# 51control.net
KiCad netlist of a schematic drawn in Altium Designer
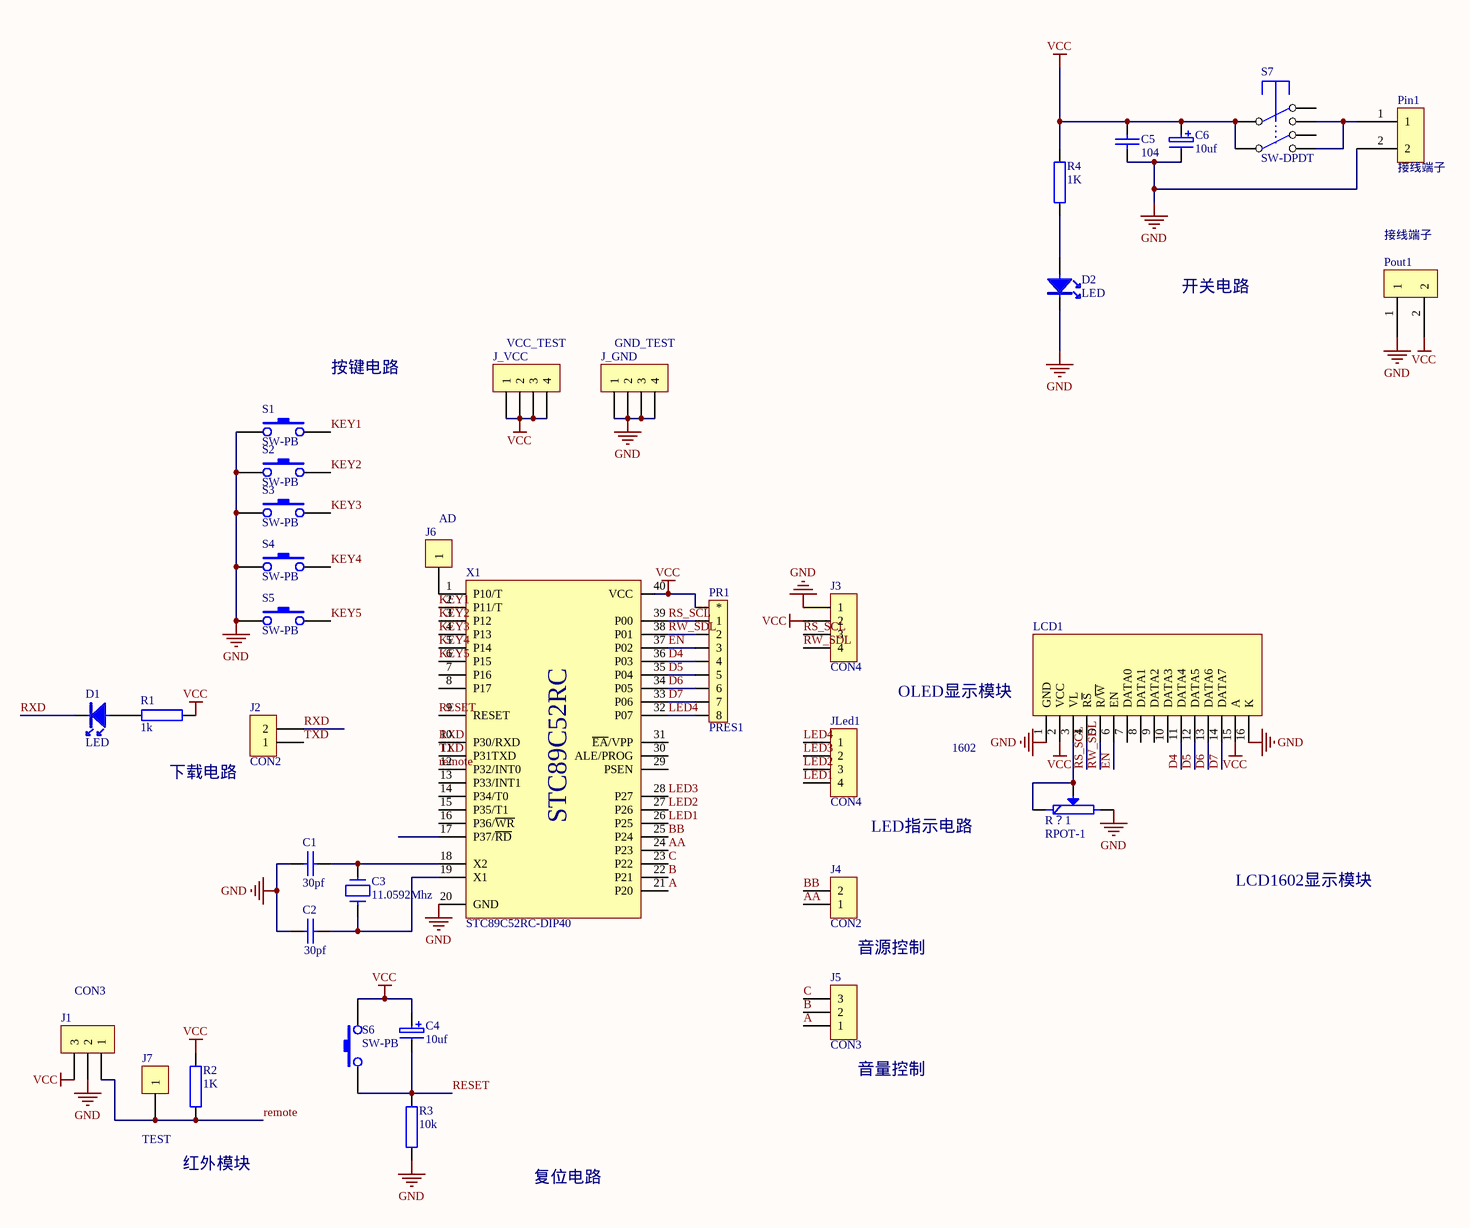
[diagram p0: 51control.SchDoc]

(export (version "E")
  (design (tool "Eeschema 10.0.6"))
  (components
    (comp (ref "C1") (value "30pf") (footprint "CAP2") (libsource (lib "电容") (part "CAP1")))
    (comp (ref "C2") (value "30pf") (footprint "CAP2") (libsource (lib "电容") (part "CAP1")))
    (comp (ref "C3") (value "11.0592Mhz") (footprint "XTAL1") (libsource (lib "晶振") (part "CPY")))
    (comp (ref "C4") (value "10uf") (footprint "CAO1") (libsource (lib "电容") (part "CAP3")))
    (comp (ref "C5") (value "104") (footprint "CAP2") (libsource (lib "电容") (part "CAP1")))
    (comp (ref "C6") (value "10uf") (footprint "CAO2") (libsource (lib "电容") (part "CAP3")))
    (comp (ref "D1") (value "LED") (footprint "LED2_B") (libsource (lib "二极管") (part "LED")))
    (comp (ref "D2") (value "LED") (footprint "LED2_B") (libsource (lib "二极管") (part "LED")))
    (comp (ref "J1")
      (value "CON3")
      (footprint "sip-3")
      (description "Connector")
      (libsource (lib "") (part "CON3_1"))
    )
    (comp (ref "J2")
      (value "CON2")
      (footprint "sip-2")
      (description "Connector")
      (libsource (lib "") (part "CON2_1"))
    )
    (comp (ref "J3")
      (value "CON4")
      (footprint "sip-4")
      (description "Connector")
      (libsource (lib "") (part "CON4_1"))
    )
    (comp (ref "J4")
      (value "CON2")
      (footprint "sip-2")
      (description "Connector")
      (libsource (lib "排针") (part "CON2"))
    )
    (comp (ref "J5")
      (value "CON3")
      (footprint "sip-3")
      (description "Connector")
      (libsource (lib "排针") (part "CON3"))
    )
    (comp (ref "J6")
      (value "AD")
      (footprint "SIP-1")
      (description "Connector")
      (libsource (lib "排针") (part "CON1"))
    )
    (comp (ref "J7")
      (value "TEST")
      (footprint "SIP-1")
      (description "Connector")
      (libsource (lib "排针") (part "CON1"))
    )
    (comp (ref "JLed1")
      (value "CON4")
      (footprint "sip-4")
      (description "Connector")
      (libsource (lib "") (part "CON4_1"))
    )
    (comp (ref "J_GND")
      (value "GND_TEST")
      (footprint "sip-4")
      (description "Connector")
      (libsource (lib "排针") (part "CON4"))
    )
    (comp (ref "J_VCC")
      (value "VCC_TEST")
      (footprint "sip-4")
      (description "Connector")
      (libsource (lib "排针") (part "CON4"))
    )
    (comp (ref "LCD1") (value "1602") (footprint "1602") (libsource (lib "液晶_数码管") (part "1602")))
    (comp (ref "Pin1") (value "接线端子") (footprint "音频功放自画库:接线端子") (libsource (lib "") (part "接线端子_1")))
    (comp (ref "Pout1") (value "接线端子") (footprint "音频功放自画库:接线端子") (libsource (lib "音频功放自画库") (part "接线端子")))
    (comp (ref "PR1") (value "PRES1") (footprint "RP1") (libsource (lib "电阻") (part "PRES1")))
    (comp (ref "R1")
      (value "1k")
      (footprint "AXIAL0.5")
      (description "电阻")
      (libsource (lib "电阻") (part "RES"))
    )
    (comp (ref "R2")
      (value "1K")
      (footprint "AXIAL0.5")
      (description "电阻")
      (libsource (lib "电阻") (part "RES"))
    )
    (comp (ref "R3")
      (value "10k")
      (footprint "AXIAL0.5")
      (description "电阻")
      (libsource (lib "电阻") (part "RES"))
    )
    (comp (ref "R4")
      (value "1K")
      (footprint "AXIAL0.5")
      (description "电阻")
      (libsource (lib "电阻") (part "RES"))
    )
    (comp (ref "R？1")
      (value "RPOT-1")
      (footprint "RVR-2")
      (description "普通电位器")
      (libsource (lib "电阻") (part "RPOT-1"))
    )
    (comp (ref "S1") (value "SW-PB") (footprint "SW6*6") (libsource (lib "开关") (part "SW-PB")))
    (comp (ref "S2") (value "SW-PB") (footprint "SW6*6") (libsource (lib "开关") (part "SW-PB")))
    (comp (ref "S3") (value "SW-PB") (footprint "SW6*6") (libsource (lib "开关") (part "SW-PB")))
    (comp (ref "S4") (value "SW-PB") (footprint "SW6*6") (libsource (lib "开关") (part "SW-PB")))
    (comp (ref "S5") (value "SW-PB") (footprint "SW6*6") (libsource (lib "开关") (part "SW-PB")))
    (comp (ref "S6") (value "SW-PB") (footprint "SW6*6") (libsource (lib "开关") (part "SW-PB")))
    (comp (ref "S7") (value "SW-DPDT") (footprint "SWH8*8") (libsource (lib "开关") (part "SW-DPDT")))
    (comp (ref "X1")
      (value "STC89C52RC-DIP40")
      (footprint "DIP-40SJ")
      (libsource (lib "单片机") (part "STC89C52RC-DIP40"))
    )
  )
  (nets
    (net (code "1") (name "/A") (class "Default")
      (node (ref "J5") (pin "1") (pinfunction "1_1") (pintype "passive"))
      (node (ref "X1") (pin "21") (pinfunction "P20_21") (pintype "passive"))
    )
    (net (code "2") (name "/AA") (class "Default")
      (node (ref "J4") (pin "1") (pinfunction "1_1") (pintype "passive"))
      (node (ref "X1") (pin "24") (pinfunction "P23_24") (pintype "passive"))
    )
    (net (code "3") (name "/B") (class "Default")
      (node (ref "J5") (pin "2") (pinfunction "2_2") (pintype "passive"))
      (node (ref "X1") (pin "22") (pinfunction "P21_22") (pintype "passive"))
    )
    (net (code "4") (name "/BB") (class "Default")
      (node (ref "J4") (pin "2") (pinfunction "2_2") (pintype "passive"))
      (node (ref "X1") (pin "25") (pinfunction "P24_25") (pintype "passive"))
    )
    (net (code "5") (name "/C") (class "Default")
      (node (ref "J5") (pin "3") (pinfunction "3_3") (pintype "passive"))
      (node (ref "X1") (pin "23") (pinfunction "P22_23") (pintype "passive"))
    )
    (net (code "6") (name "/D4") (class "Default")
      (node (ref "LCD1") (pin "11") (pinfunction "DATA4_11") (pintype "passive"))
      (node (ref "PR1") (pin "5") (pinfunction "4_5") (pintype "passive"))
      (node (ref "X1") (pin "36") (pinfunction "P03_36") (pintype "passive"))
    )
    (net (code "7") (name "/D5") (class "Default")
      (node (ref "LCD1") (pin "12") (pinfunction "DATA5_12") (pintype "passive"))
      (node (ref "PR1") (pin "6") (pinfunction "5_6") (pintype "passive"))
      (node (ref "X1") (pin "35") (pinfunction "P04_35") (pintype "passive"))
    )
    (net (code "8") (name "/D6") (class "Default")
      (node (ref "LCD1") (pin "13") (pinfunction "DATA6_13") (pintype "passive"))
      (node (ref "PR1") (pin "7") (pinfunction "6_7") (pintype "passive"))
      (node (ref "X1") (pin "34") (pinfunction "P05_34") (pintype "passive"))
    )
    (net (code "9") (name "/D7") (class "Default")
      (node (ref "LCD1") (pin "14") (pinfunction "DATA7_14") (pintype "passive"))
      (node (ref "PR1") (pin "8") (pinfunction "7_8") (pintype "passive"))
      (node (ref "X1") (pin "33") (pinfunction "P06_33") (pintype "passive"))
    )
    (net (code "10") (name "/EN") (class "Default")
      (node (ref "LCD1") (pin "6") (pinfunction "EN_6") (pintype "passive"))
      (node (ref "PR1") (pin "4") (pinfunction "3_4") (pintype "passive"))
      (node (ref "X1") (pin "37") (pinfunction "P02_37") (pintype "passive"))
    )
    (net (code "11") (name "/KEY1") (class "Default")
      (node (ref "S1") (pin "2") (pinfunction "2_2") (pintype "passive"))
      (node (ref "X1") (pin "2") (pinfunction "P11/T_2") (pintype "passive"))
    )
    (net (code "12") (name "/KEY2") (class "Default")
      (node (ref "S2") (pin "2") (pinfunction "2_2") (pintype "passive"))
      (node (ref "X1") (pin "3") (pinfunction "P12_3") (pintype "passive"))
    )
    (net (code "13") (name "/KEY3") (class "Default")
      (node (ref "S3") (pin "2") (pinfunction "2_2") (pintype "passive"))
      (node (ref "X1") (pin "4") (pinfunction "P13_4") (pintype "passive"))
    )
    (net (code "14") (name "/KEY4") (class "Default")
      (node (ref "S4") (pin "2") (pinfunction "2_2") (pintype "passive"))
      (node (ref "X1") (pin "5") (pinfunction "P14_5") (pintype "passive"))
    )
    (net (code "15") (name "/KEY5") (class "Default")
      (node (ref "S5") (pin "2") (pinfunction "2_2") (pintype "passive"))
      (node (ref "X1") (pin "6") (pinfunction "P15_6") (pintype "passive"))
    )
    (net (code "16") (name "/LED1") (class "Default")
      (node (ref "JLed1") (pin "4") (pinfunction "4_4") (pintype "passive"))
      (node (ref "X1") (pin "26") (pinfunction "P25_26") (pintype "passive"))
    )
    (net (code "17") (name "/LED2") (class "Default")
      (node (ref "JLed1") (pin "3") (pinfunction "3_3") (pintype "passive"))
      (node (ref "X1") (pin "27") (pinfunction "P26_27") (pintype "passive"))
    )
    (net (code "18") (name "/LED3") (class "Default")
      (node (ref "JLed1") (pin "2") (pinfunction "2_2") (pintype "passive"))
      (node (ref "X1") (pin "28") (pinfunction "P27_28") (pintype "passive"))
    )
    (net (code "19") (name "/LED4") (class "Default")
      (node (ref "JLed1") (pin "1") (pinfunction "1_1") (pintype "passive"))
      (node (ref "PR1") (pin "9") (pinfunction "8_9") (pintype "passive"))
      (node (ref "X1") (pin "32") (pinfunction "P07_32") (pintype "passive"))
    )
    (net (code "20") (name "/RESET") (class "Default")
      (node (ref "C4") (pin "2") (pintype "passive"))
      (node (ref "R3") (pin "2") (pinfunction "2_2") (pintype "passive"))
      (node (ref "S6") (pin "1") (pinfunction "1_1") (pintype "passive"))
      (node (ref "X1") (pin "9") (pinfunction "RESET_9") (pintype "passive"))
    )
    (net (code "21") (name "/RS_SCL") (class "Default")
      (node (ref "J3") (pin "3") (pinfunction "3_3") (pintype "passive"))
      (node (ref "LCD1") (pin "4") (pinfunction "R~{S}_4") (pintype "passive"))
      (node (ref "PR1") (pin "2") (pinfunction "1_2") (pintype "passive"))
      (node (ref "X1") (pin "39") (pinfunction "P00_39") (pintype "passive"))
    )
    (net (code "22") (name "/RW_SDL") (class "Default")
      (node (ref "J3") (pin "4") (pinfunction "4_4") (pintype "passive"))
      (node (ref "LCD1") (pin "5") (pinfunction "R/~{W}_5") (pintype "passive"))
      (node (ref "PR1") (pin "3") (pinfunction "2_3") (pintype "passive"))
      (node (ref "X1") (pin "38") (pinfunction "P01_38") (pintype "passive"))
    )
    (net (code "23") (name "/RXD") (class "Default")
      (node (ref "D1") (pin "2") (pinfunction "2_2") (pintype "passive"))
      (node (ref "J2") (pin "2") (pinfunction "2_2") (pintype "passive"))
      (node (ref "X1") (pin "10") (pinfunction "P30/RXD_10") (pintype "passive"))
    )
    (net (code "24") (name "/TXD") (class "Default")
      (node (ref "J2") (pin "1") (pinfunction "1_1") (pintype "passive"))
      (node (ref "X1") (pin "11") (pinfunction "P31TXD_11") (pintype "passive"))
    )
    (net (code "25") (name "/remote") (class "Default")
      (node (ref "J1") (pin "1") (pinfunction "1_1") (pintype "passive"))
      (node (ref "J7") (pin "1") (pinfunction "1_1") (pintype "passive"))
      (node (ref "R2") (pin "1") (pinfunction "1_1") (pintype "passive"))
      (node (ref "X1") (pin "12") (pinfunction "P32/INT0_12") (pintype "passive"))
    )
    (net (code "26") (name "GND") (class "Default")
      (node (ref "C1") (pin "2") (pinfunction "2_2") (pintype "passive"))
      (node (ref "C2") (pin "2") (pinfunction "2_2") (pintype "passive"))
      (node (ref "C5") (pin "2") (pinfunction "2_2") (pintype "passive"))
      (node (ref "C6") (pin "2") (pintype "passive"))
      (node (ref "D2") (pin "2") (pinfunction "2_2") (pintype "passive"))
      (node (ref "J1") (pin "2") (pinfunction "2_2") (pintype "passive"))
      (node (ref "J3") (pin "1") (pinfunction "1_1") (pintype "passive"))
      (node (ref "J_GND") (pin "1") (pinfunction "1_1") (pintype "passive"))
      (node (ref "J_GND") (pin "2") (pinfunction "2_2") (pintype "passive"))
      (node (ref "J_GND") (pin "3") (pinfunction "3_3") (pintype "passive"))
      (node (ref "J_GND") (pin "4") (pinfunction "4_4") (pintype "passive"))
      (node (ref "LCD1") (pin "1") (pinfunction "GND_1") (pintype "passive"))
      (node (ref "LCD1") (pin "16") (pinfunction "K_16") (pintype "passive"))
      (node (ref "Pin1") (pin "2") (pinfunction "2_2") (pintype "passive"))
      (node (ref "Pout1") (pin "1") (pinfunction "1_1") (pintype "passive"))
      (node (ref "R3") (pin "1") (pinfunction "1_1") (pintype "passive"))
      (node (ref "R？1") (pin "3") (pinfunction "3_3") (pintype "passive"))
      (node (ref "S1") (pin "1") (pinfunction "1_1") (pintype "passive"))
      (node (ref "S2") (pin "1") (pinfunction "1_1") (pintype "passive"))
      (node (ref "S3") (pin "1") (pinfunction "1_1") (pintype "passive"))
      (node (ref "S4") (pin "1") (pinfunction "1_1") (pintype "passive"))
      (node (ref "S5") (pin "1") (pinfunction "1_1") (pintype "passive"))
      (node (ref "X1") (pin "20") (pinfunction "GND_20") (pintype "passive"))
    )
    (net (code "27") (name "Net-(D1-Pad1)") (class "Default")
      (node (ref "D1") (pin "1") (pinfunction "1_1") (pintype "passive"))
      (node (ref "R1") (pin "2") (pinfunction "2_2") (pintype "passive"))
    )
    (net (code "28") (name "Net-(D2-Pad1)") (class "Default")
      (node (ref "D2") (pin "1") (pinfunction "1_1") (pintype "passive"))
      (node (ref "R4") (pin "1") (pinfunction "1_1") (pintype "passive"))
    )
    (net (code "29") (name "Net-(LCD1-VL)") (class "Default")
      (node (ref "LCD1") (pin "3") (pinfunction "VL_3") (pintype "passive"))
      (node (ref "R？1") (pin "1") (pinfunction "1_1") (pintype "passive"))
      (node (ref "R？1") (pin "2") (pinfunction "M_2") (pintype "passive"))
    )
    (net (code "30") (name "Net-(Pin1-Pad1)") (class "Default")
      (node (ref "Pin1") (pin "1") (pinfunction "1_1") (pintype "passive"))
      (node (ref "S7") (pin "3") (pinfunction "3_3") (pintype "passive"))
      (node (ref "S7") (pin "4") (pinfunction "4_4") (pintype "passive"))
    )
    (net (code "31") (name "Net-(X1-P10{slash}T)") (class "Default")
      (node (ref "J6") (pin "1") (pinfunction "1_1") (pintype "passive"))
      (node (ref "X1") (pin "1") (pinfunction "P10/T_1") (pintype "passive"))
    )
    (net (code "32") (name "Net-(X1-X1)") (class "Default")
      (node (ref "C2") (pin "1") (pinfunction "1_1") (pintype "passive"))
      (node (ref "C3") (pin "1") (pintype "passive"))
      (node (ref "X1") (pin "19") (pinfunction "X1_19") (pintype "passive"))
    )
    (net (code "33") (name "Net-(X1-X2)") (class "Default")
      (node (ref "C1") (pin "1") (pinfunction "1_1") (pintype "passive"))
      (node (ref "C3") (pin "2") (pintype "passive"))
      (node (ref "X1") (pin "18") (pinfunction "X2_18") (pintype "passive"))
    )
    (net (code "34") (name "VCC") (class "Default")
      (node (ref "C4") (pin "1") (pintype "passive"))
      (node (ref "C5") (pin "1") (pinfunction "1_1") (pintype "passive"))
      (node (ref "C6") (pin "1") (pintype "passive"))
      (node (ref "J1") (pin "3") (pinfunction "3_3") (pintype "passive"))
      (node (ref "J3") (pin "2") (pinfunction "2_2") (pintype "passive"))
      (node (ref "J_VCC") (pin "1") (pinfunction "1_1") (pintype "passive"))
      (node (ref "J_VCC") (pin "2") (pinfunction "2_2") (pintype "passive"))
      (node (ref "J_VCC") (pin "3") (pinfunction "3_3") (pintype "passive"))
      (node (ref "J_VCC") (pin "4") (pinfunction "4_4") (pintype "passive"))
      (node (ref "LCD1") (pin "15") (pinfunction "A_15") (pintype "passive"))
      (node (ref "LCD1") (pin "2") (pinfunction "VCC_2") (pintype "passive"))
      (node (ref "PR1") (pin "1") (pinfunction "*_1") (pintype "passive"))
      (node (ref "Pout1") (pin "2") (pinfunction "2_2") (pintype "passive"))
      (node (ref "R1") (pin "1") (pinfunction "1_1") (pintype "passive"))
      (node (ref "R2") (pin "2") (pinfunction "2_2") (pintype "passive"))
      (node (ref "R4") (pin "2") (pinfunction "2_2") (pintype "passive"))
      (node (ref "S6") (pin "2") (pinfunction "2_2") (pintype "passive"))
      (node (ref "S7") (pin "2") (pinfunction "2_2") (pintype "passive"))
      (node (ref "S7") (pin "5") (pinfunction "5_5") (pintype "passive"))
      (node (ref "X1") (pin "40") (pinfunction "VCC_40") (pintype "passive"))
    )
    (net (code "35") (name "unconnected-(LCD1-DATA0-Pad7)") (class "Default")
      (node (ref "LCD1") (pin "7") (pinfunction "DATA0_7") (pintype "passive"))
    )
    (net (code "36") (name "unconnected-(LCD1-DATA1-Pad8)") (class "Default")
      (node (ref "LCD1") (pin "8") (pinfunction "DATA1_8") (pintype "passive"))
    )
    (net (code "37") (name "unconnected-(LCD1-DATA2-Pad9)") (class "Default")
      (node (ref "LCD1") (pin "9") (pinfunction "DATA2_9") (pintype "passive"))
    )
    (net (code "38") (name "unconnected-(LCD1-DATA3-Pad10)") (class "Default")
      (node (ref "LCD1") (pin "10") (pinfunction "DATA3_10") (pintype "passive"))
    )
    (net (code "39") (name "unconnected-(S7-Pad1)") (class "Default")
      (node (ref "S7") (pin "1") (pinfunction "1_1") (pintype "passive"))
    )
    (net (code "40") (name "unconnected-(S7-Pad6)") (class "Default")
      (node (ref "S7") (pin "6") (pinfunction "6_6") (pintype "passive"))
    )
    (net (code "41") (name "unconnected-(X1-ALE{slash}PROG-Pad30)") (class "Default")
      (node (ref "X1") (pin "30") (pinfunction "ALE/PROG_30") (pintype "passive"))
    )
    (net (code "42") (name "unconnected-(X1-P16-Pad7)") (class "Default")
      (node (ref "X1") (pin "7") (pinfunction "P16_7") (pintype "passive"))
    )
    (net (code "43") (name "unconnected-(X1-P17-Pad8)") (class "Default")
      (node (ref "X1") (pin "8") (pinfunction "P17_8") (pintype "passive"))
    )
    (net (code "44") (name "unconnected-(X1-P33{slash}INT1-Pad13)") (class "Default")
      (node (ref "X1") (pin "13") (pinfunction "P33/INT1_13") (pintype "passive"))
    )
    (net (code "45") (name "unconnected-(X1-P34{slash}T0-Pad14)") (class "Default")
      (node (ref "X1") (pin "14") (pinfunction "P34/T0_14") (pintype "passive"))
    )
    (net (code "46") (name "unconnected-(X1-P35{slash}T1-Pad15)") (class "Default")
      (node (ref "X1") (pin "15") (pinfunction "P35/T1_15") (pintype "passive"))
    )
    (net (code "47") (name "unconnected-(X1-P36{slash}~{WR}-Pad16)") (class "Default")
      (node (ref "X1") (pin "16") (pinfunction "P36/~{WR}_16") (pintype "passive"))
    )
    (net (code "48") (name "unconnected-(X1-P37{slash}~{RD}-Pad17)") (class "Default")
      (node (ref "X1") (pin "17") (pinfunction "P37/~{RD}_17") (pintype "passive"))
    )
    (net (code "49") (name "unconnected-(X1-PSEN-Pad29)") (class "Default")
      (node (ref "X1") (pin "29") (pinfunction "PSEN_29") (pintype "passive"))
    )
    (net (code "50") (name "unconnected-(X1-~{EA}{slash}VPP-Pad31)") (class "Default")
      (node (ref "X1") (pin "31") (pinfunction "~{EA}/VPP_31") (pintype "passive"))
    )
  )
)
